# Cokpit_V3-_AutoPilot.net
KiCad netlist of a schematic drawn in EasyEDA
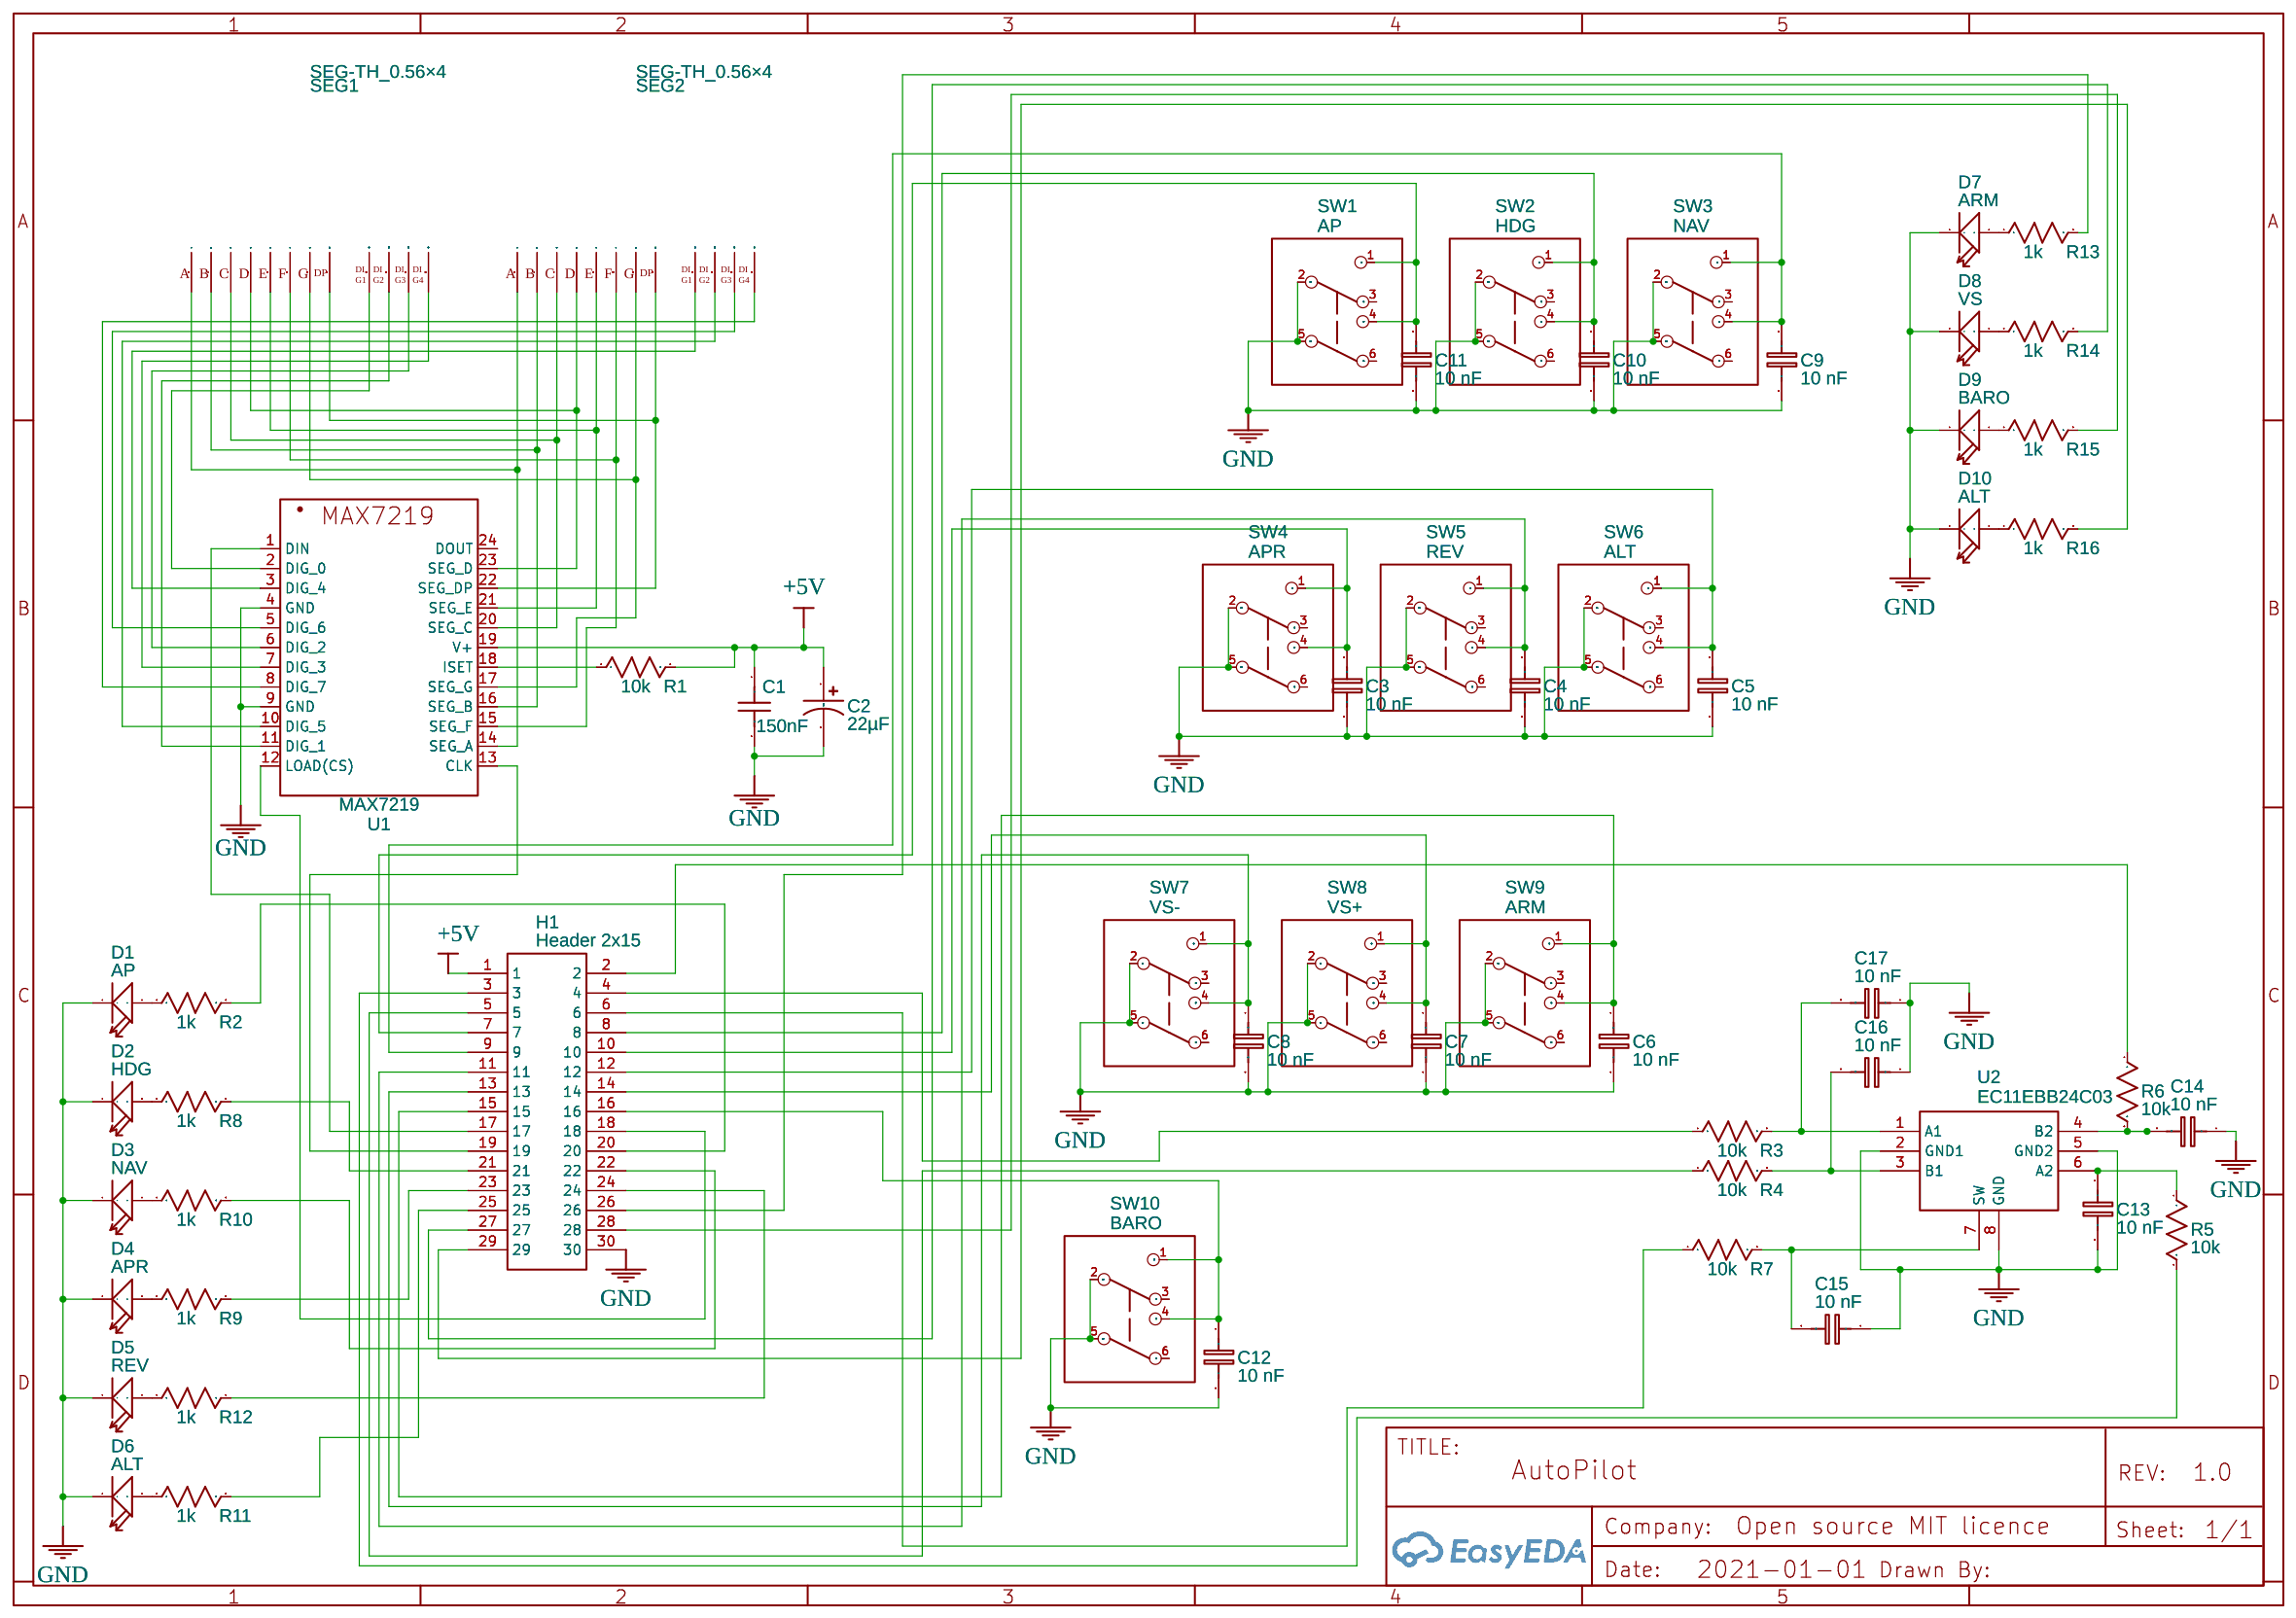
[diagram p0: schematic sheet]

(export (version "E")
  (design (tool "Eeschema 10.0.6"))
  (components
    (comp (ref "C1") (value "150nF") (libsource (lib "") (part "C_0201_US")))
    (comp (ref "C2") (value "22µF") (libsource (lib "") (part "C_Tan_SMD_A_US")))
    (comp (ref "C3") (value "10 nF") (libsource (lib "") (part "Capacitor1_EU_1")))
    (comp (ref "C4") (value "10 nF") (libsource (lib "") (part "Capacitor1_EU_1")))
    (comp (ref "C5") (value "10 nF") (libsource (lib "") (part "Capacitor1_EU_1")))
    (comp (ref "C6") (value "10 nF") (libsource (lib "") (part "Capacitor1_EU_1")))
    (comp (ref "C7") (value "10 nF") (libsource (lib "") (part "Capacitor1_EU_1")))
    (comp (ref "C8") (value "10 nF") (libsource (lib "") (part "Capacitor1_EU_1")))
    (comp (ref "C9") (value "10 nF") (libsource (lib "") (part "Capacitor1_EU")))
    (comp (ref "C10") (value "10 nF") (libsource (lib "") (part "Capacitor1_EU")))
    (comp (ref "C11") (value "10 nF") (libsource (lib "") (part "Capacitor1_EU")))
    (comp (ref "C12") (value "10 nF") (libsource (lib "") (part "Capacitor1_EU")))
    (comp (ref "C13") (value "10 nF") (libsource (lib "") (part "Capacitor1_EU_1")))
    (comp (ref "C14") (value "10 nF") (libsource (lib "") (part "Capacitor1_EU_2")))
    (comp (ref "C15") (value "10 nF") (libsource (lib "") (part "Capacitor1_EU_2")))
    (comp (ref "C16") (value "10 nF") (libsource (lib "") (part "Capacitor1_EU_2")))
    (comp (ref "C17") (value "10 nF") (libsource (lib "") (part "Capacitor1_EU_2")))
    (comp (ref "D1")
      (value "AP")
      (fields (field (name "BOM_Manufacturer Part") "?"))
      (libsource (lib "") (part "DIP LED Red-Red;"))
    )
    (comp (ref "D2")
      (value "HDG")
      (fields (field (name "BOM_Manufacturer Part") "?"))
      (libsource (lib "") (part "DIP LED Red-Red;"))
    )
    (comp (ref "D3")
      (value "NAV")
      (fields (field (name "BOM_Manufacturer Part") "?"))
      (libsource (lib "") (part "DIP LED Red-Red;"))
    )
    (comp (ref "D4")
      (value "APR")
      (fields (field (name "BOM_Manufacturer Part") "?"))
      (libsource (lib "") (part "DIP LED Red-Red;"))
    )
    (comp (ref "D5")
      (value "REV")
      (fields (field (name "BOM_Manufacturer Part") "?"))
      (libsource (lib "") (part "DIP LED Red-Red;"))
    )
    (comp (ref "D6")
      (value "ALT")
      (fields (field (name "BOM_Manufacturer Part") "?"))
      (libsource (lib "") (part "DIP LED Red-Red;"))
    )
    (comp (ref "D7")
      (value "ARM")
      (fields (field (name "BOM_Manufacturer Part") "?"))
      (libsource (lib "") (part "DIP LED Red-Red;"))
    )
    (comp (ref "D8")
      (value "VS")
      (fields (field (name "BOM_Manufacturer Part") "?"))
      (libsource (lib "") (part "DIP LED Red-Red;"))
    )
    (comp (ref "D9")
      (value "BARO")
      (fields (field (name "BOM_Manufacturer Part") "?"))
      (libsource (lib "") (part "DIP LED Red-Red;"))
    )
    (comp (ref "D10")
      (value "ALT")
      (fields (field (name "BOM_Manufacturer Part") "?"))
      (libsource (lib "") (part "DIP LED Red-Red;"))
    )
    (comp (ref "H1") (value "Header 2x15") (libsource (lib "") (part "Header 2x15")))
    (comp (ref "R1") (value "10k") (libsource (lib "") (part "R_0201_US")))
    (comp (ref "R2") (value "1k") (libsource (lib "") (part "R_0201_US")))
    (comp (ref "R3") (value "10k") (libsource (lib "") (part "R_0201_US")))
    (comp (ref "R4") (value "10k") (libsource (lib "") (part "R_0201_US")))
    (comp (ref "R5") (value "10k") (libsource (lib "") (part "R_0201_US_1")))
    (comp (ref "R6") (value "10k") (libsource (lib "") (part "R_0201_US_1")))
    (comp (ref "R7") (value "10k") (libsource (lib "") (part "R_0201_US")))
    (comp (ref "R8") (value "1k") (libsource (lib "") (part "R_0201_US")))
    (comp (ref "R9") (value "1k") (libsource (lib "") (part "R_0201_US")))
    (comp (ref "R10") (value "1k") (libsource (lib "") (part "R_0201_US")))
    (comp (ref "R11") (value "1k") (libsource (lib "") (part "R_0201_US")))
    (comp (ref "R12") (value "1k") (libsource (lib "") (part "R_0201_US")))
    (comp (ref "R13") (value "1k") (libsource (lib "") (part "R_0201_US")))
    (comp (ref "R14") (value "1k") (libsource (lib "") (part "R_0201_US")))
    (comp (ref "R15") (value "1k") (libsource (lib "") (part "R_0201_US")))
    (comp (ref "R16") (value "1k") (libsource (lib "") (part "R_0201_US")))
    (comp (ref "SEG1")
      (value "SEG-TH_0.56×4")
      (fields (field (name "BOM_Supplier Part") "C109200"))
      (libsource (lib "") (part "SEG-TH_0.56×4"))
    )
    (comp (ref "SEG2")
      (value "SEG-TH_0.56×4")
      (fields (field (name "BOM_Supplier Part") "C109200"))
      (libsource (lib "") (part "SEG-TH_0.56×4"))
    )
    (comp (ref "SW1") (value "AP") (libsource (lib "") (part "SW_PUSH_DPDT_MINI_7x7")))
    (comp (ref "SW2") (value "HDG") (libsource (lib "") (part "SW_PUSH_DPDT_MINI_7x7")))
    (comp (ref "SW3") (value "NAV") (libsource (lib "") (part "SW_PUSH_DPDT_MINI_7x7")))
    (comp (ref "SW4") (value "APR") (libsource (lib "") (part "SW_PUSH_DPDT_MINI_7x7")))
    (comp (ref "SW5") (value "REV") (libsource (lib "") (part "SW_PUSH_DPDT_MINI_7x7")))
    (comp (ref "SW6") (value "ALT") (libsource (lib "") (part "SW_PUSH_DPDT_MINI_7x7")))
    (comp (ref "SW7") (value "VS-") (libsource (lib "") (part "SW_PUSH_DPDT_MINI_7x7")))
    (comp (ref "SW8") (value "VS+") (libsource (lib "") (part "SW_PUSH_DPDT_MINI_7x7")))
    (comp (ref "SW9") (value "ARM") (libsource (lib "") (part "SW_PUSH_DPDT_MINI_7x7")))
    (comp (ref "SW10") (value "BARO") (libsource (lib "") (part "SW_PUSH_DPDT_MINI_7x7")))
    (comp (ref "U1")
      (value "MAX7219")
      (fields (field (name "BOM_Manufacturer Part") "MAXIM") (field (name "BOM_Supplier Part") "C129565"))
      (libsource (lib "") (part "MAX7219"))
    )
    (comp (ref "U2") (value "EC11EBB24C03") (libsource (lib "") (part "EC11EBB24C03")))
  )
  (nets
    (net (code "1") (name "+5V") (class "Default")
      (node (ref "C1") (pin "1") (pinfunction "1_1") (pintype "unspecified"))
      (node (ref "C2") (pin "1") (pinfunction "1_1") (pintype "unspecified"))
      (node (ref "H1") (pin "1") (pinfunction "1_1") (pintype "unspecified"))
      (node (ref "R1") (pin "2") (pinfunction "2_2") (pintype "unspecified"))
      (node (ref "U1") (pin "19") (pinfunction "V+_19") (pintype "unspecified"))
    )
    (net (code "2") (name "GND") (class "Default")
      (node (ref "C1") (pin "2") (pinfunction "2_2") (pintype "unspecified"))
      (node (ref "C10") (pin "2") (pinfunction "2_2") (pintype "unspecified"))
      (node (ref "C11") (pin "2") (pinfunction "2_2") (pintype "unspecified"))
      (node (ref "C12") (pin "2") (pinfunction "2_2") (pintype "unspecified"))
      (node (ref "C13") (pin "2") (pinfunction "2_2") (pintype "unspecified"))
      (node (ref "C14") (pin "1") (pinfunction "1_1") (pintype "unspecified"))
      (node (ref "C15") (pin "1") (pinfunction "1_1") (pintype "unspecified"))
      (node (ref "C16") (pin "1") (pinfunction "1_1") (pintype "unspecified"))
      (node (ref "C17") (pin "1") (pinfunction "1_1") (pintype "unspecified"))
      (node (ref "C2") (pin "2") (pinfunction "2_2") (pintype "unspecified"))
      (node (ref "C3") (pin "2") (pinfunction "2_2") (pintype "unspecified"))
      (node (ref "C4") (pin "2") (pinfunction "2_2") (pintype "unspecified"))
      (node (ref "C5") (pin "2") (pinfunction "2_2") (pintype "unspecified"))
      (node (ref "C6") (pin "2") (pinfunction "2_2") (pintype "unspecified"))
      (node (ref "C7") (pin "2") (pinfunction "2_2") (pintype "unspecified"))
      (node (ref "C8") (pin "2") (pinfunction "2_2") (pintype "unspecified"))
      (node (ref "C9") (pin "2") (pinfunction "2_2") (pintype "unspecified"))
      (node (ref "D1") (pin "K") (pinfunction "-_K") (pintype "unspecified"))
      (node (ref "D10") (pin "K") (pinfunction "-_K") (pintype "unspecified"))
      (node (ref "D2") (pin "K") (pinfunction "-_K") (pintype "unspecified"))
      (node (ref "D3") (pin "K") (pinfunction "-_K") (pintype "unspecified"))
      (node (ref "D4") (pin "K") (pinfunction "-_K") (pintype "unspecified"))
      (node (ref "D5") (pin "K") (pinfunction "-_K") (pintype "unspecified"))
      (node (ref "D6") (pin "K") (pinfunction "-_K") (pintype "unspecified"))
      (node (ref "D7") (pin "K") (pinfunction "-_K") (pintype "unspecified"))
      (node (ref "D8") (pin "K") (pinfunction "-_K") (pintype "unspecified"))
      (node (ref "D9") (pin "K") (pinfunction "-_K") (pintype "unspecified"))
      (node (ref "H1") (pin "30") (pinfunction "30_30") (pintype "unspecified"))
      (node (ref "SW1") (pin "2") (pinfunction "COM1_2") (pintype "unspecified"))
      (node (ref "SW1") (pin "5") (pinfunction "COM2_5") (pintype "unspecified"))
      (node (ref "SW10") (pin "2") (pinfunction "COM1_2") (pintype "unspecified"))
      (node (ref "SW10") (pin "5") (pinfunction "COM2_5") (pintype "unspecified"))
      (node (ref "SW2") (pin "2") (pinfunction "COM1_2") (pintype "unspecified"))
      (node (ref "SW2") (pin "5") (pinfunction "COM2_5") (pintype "unspecified"))
      (node (ref "SW3") (pin "2") (pinfunction "COM1_2") (pintype "unspecified"))
      (node (ref "SW3") (pin "5") (pinfunction "COM2_5") (pintype "unspecified"))
      (node (ref "SW4") (pin "2") (pinfunction "COM1_2") (pintype "unspecified"))
      (node (ref "SW4") (pin "5") (pinfunction "COM2_5") (pintype "unspecified"))
      (node (ref "SW5") (pin "2") (pinfunction "COM1_2") (pintype "unspecified"))
      (node (ref "SW5") (pin "5") (pinfunction "COM2_5") (pintype "unspecified"))
      (node (ref "SW6") (pin "2") (pinfunction "COM1_2") (pintype "unspecified"))
      (node (ref "SW6") (pin "5") (pinfunction "COM2_5") (pintype "unspecified"))
      (node (ref "SW7") (pin "2") (pinfunction "COM1_2") (pintype "unspecified"))
      (node (ref "SW7") (pin "5") (pinfunction "COM2_5") (pintype "unspecified"))
      (node (ref "SW8") (pin "2") (pinfunction "COM1_2") (pintype "unspecified"))
      (node (ref "SW8") (pin "5") (pinfunction "COM2_5") (pintype "unspecified"))
      (node (ref "SW9") (pin "2") (pinfunction "COM1_2") (pintype "unspecified"))
      (node (ref "SW9") (pin "5") (pinfunction "COM2_5") (pintype "unspecified"))
      (node (ref "U1") (pin "4") (pinfunction "GND_4") (pintype "unspecified"))
      (node (ref "U1") (pin "9") (pinfunction "GND_9") (pintype "unspecified"))
      (node (ref "U2") (pin "2") (pinfunction "GND1_2") (pintype "unspecified"))
      (node (ref "U2") (pin "5") (pinfunction "GND2_5") (pintype "unspecified"))
      (node (ref "U2") (pin "8") (pinfunction "GND_8") (pintype "unspecified"))
    )
    (net (code "3") (name "Net-(D1-+)") (class "Default")
      (node (ref "D1") (pin "A") (pinfunction "+_A") (pintype "unspecified"))
      (node (ref "R2") (pin "1") (pinfunction "1_1") (pintype "unspecified"))
    )
    (net (code "4") (name "Net-(D2-+)") (class "Default")
      (node (ref "D2") (pin "A") (pinfunction "+_A") (pintype "unspecified"))
      (node (ref "R8") (pin "1") (pinfunction "1_1") (pintype "unspecified"))
    )
    (net (code "5") (name "Net-(D3-+)") (class "Default")
      (node (ref "D3") (pin "A") (pinfunction "+_A") (pintype "unspecified"))
      (node (ref "R10") (pin "1") (pinfunction "1_1") (pintype "unspecified"))
    )
    (net (code "6") (name "Net-(D4-+)") (class "Default")
      (node (ref "D4") (pin "A") (pinfunction "+_A") (pintype "unspecified"))
      (node (ref "R9") (pin "1") (pinfunction "1_1") (pintype "unspecified"))
    )
    (net (code "7") (name "Net-(D5-+)") (class "Default")
      (node (ref "D5") (pin "A") (pinfunction "+_A") (pintype "unspecified"))
      (node (ref "R12") (pin "1") (pinfunction "1_1") (pintype "unspecified"))
    )
    (net (code "8") (name "Net-(D6-+)") (class "Default")
      (node (ref "D6") (pin "A") (pinfunction "+_A") (pintype "unspecified"))
      (node (ref "R11") (pin "1") (pinfunction "1_1") (pintype "unspecified"))
    )
    (net (code "9") (name "Net-(D7-+)") (class "Default")
      (node (ref "D7") (pin "A") (pinfunction "+_A") (pintype "unspecified"))
      (node (ref "R13") (pin "1") (pinfunction "1_1") (pintype "unspecified"))
    )
    (net (code "10") (name "Net-(D8-+)") (class "Default")
      (node (ref "D8") (pin "A") (pinfunction "+_A") (pintype "unspecified"))
      (node (ref "R14") (pin "1") (pinfunction "1_1") (pintype "unspecified"))
    )
    (net (code "11") (name "Net-(D9-+)") (class "Default")
      (node (ref "D9") (pin "A") (pinfunction "+_A") (pintype "unspecified"))
      (node (ref "R15") (pin "1") (pinfunction "1_1") (pintype "unspecified"))
    )
    (net (code "12") (name "Net-(D10-+)") (class "Default")
      (node (ref "D10") (pin "A") (pinfunction "+_A") (pintype "unspecified"))
      (node (ref "R16") (pin "1") (pinfunction "1_1") (pintype "unspecified"))
    )
    (net (code "13") (name "Net-(H1-Pad2)") (class "Default")
      (node (ref "H1") (pin "2") (pinfunction "2_2") (pintype "unspecified"))
      (node (ref "R6") (pin "1") (pinfunction "1_1") (pintype "unspecified"))
    )
    (net (code "14") (name "Net-(H1-Pad3)") (class "Default")
      (node (ref "H1") (pin "3") (pinfunction "3_3") (pintype "unspecified"))
      (node (ref "R5") (pin "2") (pinfunction "2_2") (pintype "unspecified"))
    )
    (net (code "15") (name "Net-(H1-Pad4)") (class "Default")
      (node (ref "H1") (pin "4") (pinfunction "4_4") (pintype "unspecified"))
      (node (ref "R3") (pin "1") (pinfunction "1_1") (pintype "unspecified"))
    )
    (net (code "16") (name "Net-(H1-Pad5)") (class "Default")
      (node (ref "H1") (pin "5") (pinfunction "5_5") (pintype "unspecified"))
      (node (ref "R4") (pin "1") (pinfunction "1_1") (pintype "unspecified"))
    )
    (net (code "17") (name "Net-(H1-Pad6)") (class "Default")
      (node (ref "H1") (pin "6") (pinfunction "6_6") (pintype "unspecified"))
      (node (ref "R7") (pin "1") (pinfunction "1_1") (pintype "unspecified"))
    )
    (net (code "18") (name "Net-(H1-Pad20)") (class "Default")
      (node (ref "H1") (pin "20") (pinfunction "20_20") (pintype "unspecified"))
      (node (ref "R2") (pin "2") (pinfunction "2_2") (pintype "unspecified"))
    )
    (net (code "19") (name "Net-(H1-Pad21)") (class "Default")
      (node (ref "H1") (pin "21") (pinfunction "21_21") (pintype "unspecified"))
      (node (ref "R8") (pin "2") (pinfunction "2_2") (pintype "unspecified"))
    )
    (net (code "20") (name "Net-(H1-Pad22)") (class "Default")
      (node (ref "H1") (pin "22") (pinfunction "22_22") (pintype "unspecified"))
      (node (ref "R10") (pin "2") (pinfunction "2_2") (pintype "unspecified"))
    )
    (net (code "21") (name "Net-(H1-Pad23)") (class "Default")
      (node (ref "H1") (pin "23") (pinfunction "23_23") (pintype "unspecified"))
      (node (ref "R9") (pin "2") (pinfunction "2_2") (pintype "unspecified"))
    )
    (net (code "22") (name "Net-(H1-Pad24)") (class "Default")
      (node (ref "H1") (pin "24") (pinfunction "24_24") (pintype "unspecified"))
      (node (ref "R12") (pin "2") (pinfunction "2_2") (pintype "unspecified"))
    )
    (net (code "23") (name "Net-(H1-Pad25)") (class "Default")
      (node (ref "H1") (pin "25") (pinfunction "25_25") (pintype "unspecified"))
      (node (ref "R11") (pin "2") (pinfunction "2_2") (pintype "unspecified"))
    )
    (net (code "24") (name "Net-(H1-Pad26)") (class "Default")
      (node (ref "H1") (pin "26") (pinfunction "26_26") (pintype "unspecified"))
      (node (ref "R13") (pin "2") (pinfunction "2_2") (pintype "unspecified"))
    )
    (net (code "25") (name "Net-(H1-Pad27)") (class "Default")
      (node (ref "H1") (pin "27") (pinfunction "27_27") (pintype "unspecified"))
      (node (ref "R14") (pin "2") (pinfunction "2_2") (pintype "unspecified"))
    )
    (net (code "26") (name "Net-(H1-Pad28)") (class "Default")
      (node (ref "H1") (pin "28") (pinfunction "28_28") (pintype "unspecified"))
      (node (ref "R15") (pin "2") (pinfunction "2_2") (pintype "unspecified"))
    )
    (net (code "27") (name "Net-(H1-Pad29)") (class "Default")
      (node (ref "H1") (pin "29") (pinfunction "29_29") (pintype "unspecified"))
      (node (ref "R16") (pin "2") (pinfunction "2_2") (pintype "unspecified"))
    )
    (net (code "28") (name "Net-(SEG1-A)") (class "Default")
      (node (ref "SEG1") (pin "11") (pinfunction "A_11") (pintype "input"))
      (node (ref "SEG2") (pin "11") (pinfunction "A_11") (pintype "input"))
      (node (ref "U1") (pin "14") (pinfunction "SEG_A_14") (pintype "unspecified"))
    )
    (net (code "29") (name "Net-(SEG1-B)") (class "Default")
      (node (ref "SEG1") (pin "7") (pinfunction "B_7") (pintype "input"))
      (node (ref "SEG2") (pin "7") (pinfunction "B_7") (pintype "input"))
      (node (ref "U1") (pin "16") (pinfunction "SEG_B_16") (pintype "unspecified"))
    )
    (net (code "30") (name "Net-(SEG1-C)") (class "Default")
      (node (ref "SEG1") (pin "4") (pinfunction "C_4") (pintype "input"))
      (node (ref "SEG2") (pin "4") (pinfunction "C_4") (pintype "input"))
      (node (ref "U1") (pin "20") (pinfunction "SEG_C_20") (pintype "unspecified"))
    )
    (net (code "31") (name "Net-(SEG1-D)") (class "Default")
      (node (ref "SEG1") (pin "2") (pinfunction "D_2") (pintype "input"))
      (node (ref "SEG2") (pin "2") (pinfunction "D_2") (pintype "input"))
      (node (ref "U1") (pin "23") (pinfunction "SEG_D_23") (pintype "unspecified"))
    )
    (net (code "32") (name "Net-(SEG1-DIG1)") (class "Default")
      (node (ref "SEG1") (pin "12") (pinfunction "DIG1_12") (pintype "input"))
      (node (ref "U1") (pin "2") (pinfunction "DIG_0_2") (pintype "unspecified"))
    )
    (net (code "33") (name "Net-(SEG1-DIG2)") (class "Default")
      (node (ref "SEG1") (pin "9") (pinfunction "DIG2_9") (pintype "input"))
      (node (ref "U1") (pin "11") (pinfunction "DIG_1_11") (pintype "unspecified"))
    )
    (net (code "34") (name "Net-(SEG1-DIG3)") (class "Default")
      (node (ref "SEG1") (pin "8") (pinfunction "DIG3_8") (pintype "input"))
      (node (ref "U1") (pin "6") (pinfunction "DIG_2_6") (pintype "unspecified"))
    )
    (net (code "35") (name "Net-(SEG1-DIG4)") (class "Default")
      (node (ref "SEG1") (pin "6") (pinfunction "DIG4_6") (pintype "input"))
      (node (ref "U1") (pin "7") (pinfunction "DIG_3_7") (pintype "unspecified"))
    )
    (net (code "36") (name "Net-(SEG1-DP)") (class "Default")
      (node (ref "SEG1") (pin "3") (pinfunction "DP_3") (pintype "input"))
      (node (ref "SEG2") (pin "3") (pinfunction "DP_3") (pintype "input"))
      (node (ref "U1") (pin "22") (pinfunction "SEG_DP_22") (pintype "unspecified"))
    )
    (net (code "37") (name "Net-(SEG1-E)") (class "Default")
      (node (ref "SEG1") (pin "1") (pinfunction "E_1") (pintype "input"))
      (node (ref "SEG2") (pin "1") (pinfunction "E_1") (pintype "input"))
      (node (ref "U1") (pin "21") (pinfunction "SEG_E_21") (pintype "unspecified"))
    )
    (net (code "38") (name "Net-(SEG1-F)") (class "Default")
      (node (ref "SEG1") (pin "10") (pinfunction "F_10") (pintype "input"))
      (node (ref "SEG2") (pin "10") (pinfunction "F_10") (pintype "input"))
      (node (ref "U1") (pin "15") (pinfunction "SEG_F_15") (pintype "unspecified"))
    )
    (net (code "39") (name "Net-(SEG1-G)") (class "Default")
      (node (ref "SEG1") (pin "5") (pinfunction "G_5") (pintype "input"))
      (node (ref "SEG2") (pin "5") (pinfunction "G_5") (pintype "input"))
      (node (ref "U1") (pin "17") (pinfunction "SEG_G_17") (pintype "unspecified"))
    )
    (net (code "40") (name "Net-(SEG2-DIG1)") (class "Default")
      (node (ref "SEG2") (pin "12") (pinfunction "DIG1_12") (pintype "input"))
      (node (ref "U1") (pin "3") (pinfunction "DIG_4_3") (pintype "unspecified"))
    )
    (net (code "41") (name "Net-(SEG2-DIG2)") (class "Default")
      (node (ref "SEG2") (pin "9") (pinfunction "DIG2_9") (pintype "input"))
      (node (ref "U1") (pin "10") (pinfunction "DIG_5_10") (pintype "unspecified"))
    )
    (net (code "42") (name "Net-(SEG2-DIG3)") (class "Default")
      (node (ref "SEG2") (pin "8") (pinfunction "DIG3_8") (pintype "input"))
      (node (ref "U1") (pin "5") (pinfunction "DIG_6_5") (pintype "unspecified"))
    )
    (net (code "43") (name "Net-(SEG2-DIG4)") (class "Default")
      (node (ref "SEG2") (pin "6") (pinfunction "DIG4_6") (pintype "input"))
      (node (ref "U1") (pin "8") (pinfunction "DIG_7_8") (pintype "unspecified"))
    )
    (net (code "44") (name "Net-(SW1-NO1)") (class "Default")
      (node (ref "C11") (pin "1") (pinfunction "1_1") (pintype "unspecified"))
      (node (ref "H1") (pin "7") (pinfunction "7_7") (pintype "unspecified"))
      (node (ref "SW1") (pin "1") (pinfunction "NO1_1") (pintype "unspecified"))
      (node (ref "SW1") (pin "4") (pinfunction "NO2_4") (pintype "unspecified"))
    )
    (net (code "45") (name "Net-(SW2-NO1)") (class "Default")
      (node (ref "C10") (pin "1") (pinfunction "1_1") (pintype "unspecified"))
      (node (ref "H1") (pin "8") (pinfunction "8_8") (pintype "unspecified"))
      (node (ref "SW2") (pin "1") (pinfunction "NO1_1") (pintype "unspecified"))
      (node (ref "SW2") (pin "4") (pinfunction "NO2_4") (pintype "unspecified"))
    )
    (net (code "46") (name "Net-(SW3-NO1)") (class "Default")
      (node (ref "C9") (pin "1") (pinfunction "1_1") (pintype "unspecified"))
      (node (ref "H1") (pin "9") (pinfunction "9_9") (pintype "unspecified"))
      (node (ref "SW3") (pin "1") (pinfunction "NO1_1") (pintype "unspecified"))
      (node (ref "SW3") (pin "4") (pinfunction "NO2_4") (pintype "unspecified"))
    )
    (net (code "47") (name "Net-(SW4-NO1)") (class "Default")
      (node (ref "C3") (pin "1") (pinfunction "1_1") (pintype "unspecified"))
      (node (ref "H1") (pin "10") (pinfunction "10_10") (pintype "unspecified"))
      (node (ref "SW4") (pin "1") (pinfunction "NO1_1") (pintype "unspecified"))
      (node (ref "SW4") (pin "4") (pinfunction "NO2_4") (pintype "unspecified"))
    )
    (net (code "48") (name "Net-(SW5-NO1)") (class "Default")
      (node (ref "C4") (pin "1") (pinfunction "1_1") (pintype "unspecified"))
      (node (ref "H1") (pin "11") (pinfunction "11_11") (pintype "unspecified"))
      (node (ref "SW5") (pin "1") (pinfunction "NO1_1") (pintype "unspecified"))
      (node (ref "SW5") (pin "4") (pinfunction "NO2_4") (pintype "unspecified"))
    )
    (net (code "49") (name "Net-(SW6-NO1)") (class "Default")
      (node (ref "C5") (pin "1") (pinfunction "1_1") (pintype "unspecified"))
      (node (ref "H1") (pin "12") (pinfunction "12_12") (pintype "unspecified"))
      (node (ref "SW6") (pin "1") (pinfunction "NO1_1") (pintype "unspecified"))
      (node (ref "SW6") (pin "4") (pinfunction "NO2_4") (pintype "unspecified"))
    )
    (net (code "50") (name "Net-(SW7-NO1)") (class "Default")
      (node (ref "C8") (pin "1") (pinfunction "1_1") (pintype "unspecified"))
      (node (ref "H1") (pin "13") (pinfunction "13_13") (pintype "unspecified"))
      (node (ref "SW7") (pin "1") (pinfunction "NO1_1") (pintype "unspecified"))
      (node (ref "SW7") (pin "4") (pinfunction "NO2_4") (pintype "unspecified"))
    )
    (net (code "51") (name "Net-(SW8-NO1)") (class "Default")
      (node (ref "C7") (pin "1") (pinfunction "1_1") (pintype "unspecified"))
      (node (ref "H1") (pin "14") (pinfunction "14_14") (pintype "unspecified"))
      (node (ref "SW8") (pin "1") (pinfunction "NO1_1") (pintype "unspecified"))
      (node (ref "SW8") (pin "4") (pinfunction "NO2_4") (pintype "unspecified"))
    )
    (net (code "52") (name "Net-(SW9-NO1)") (class "Default")
      (node (ref "C6") (pin "1") (pinfunction "1_1") (pintype "unspecified"))
      (node (ref "H1") (pin "15") (pinfunction "15_15") (pintype "unspecified"))
      (node (ref "SW9") (pin "1") (pinfunction "NO1_1") (pintype "unspecified"))
      (node (ref "SW9") (pin "4") (pinfunction "NO2_4") (pintype "unspecified"))
    )
    (net (code "53") (name "Net-(SW10-NO1)") (class "Default")
      (node (ref "C12") (pin "1") (pinfunction "1_1") (pintype "unspecified"))
      (node (ref "H1") (pin "16") (pinfunction "16_16") (pintype "unspecified"))
      (node (ref "SW10") (pin "1") (pinfunction "NO1_1") (pintype "unspecified"))
      (node (ref "SW10") (pin "4") (pinfunction "NO2_4") (pintype "unspecified"))
    )
    (net (code "54") (name "Net-(U1-CLK)") (class "Default")
      (node (ref "H1") (pin "19") (pinfunction "19_19") (pintype "unspecified"))
      (node (ref "U1") (pin "13") (pinfunction "CLK_13") (pintype "unspecified"))
    )
    (net (code "55") (name "Net-(U1-DIN)") (class "Default")
      (node (ref "H1") (pin "17") (pinfunction "17_17") (pintype "unspecified"))
      (node (ref "U1") (pin "1") (pinfunction "DIN_1") (pintype "unspecified"))
    )
    (net (code "56") (name "Net-(U1-ISET)") (class "Default")
      (node (ref "R1") (pin "1") (pinfunction "1_1") (pintype "unspecified"))
      (node (ref "U1") (pin "18") (pinfunction "ISET_18") (pintype "unspecified"))
    )
    (net (code "57") (name "Net-(U1-LOAD(CS))") (class "Default")
      (node (ref "H1") (pin "18") (pinfunction "18_18") (pintype "unspecified"))
      (node (ref "U1") (pin "12") (pinfunction "LOAD(CS)_12") (pintype "unspecified"))
    )
    (net (code "58") (name "Net-(U2-A1)") (class "Default")
      (node (ref "C17") (pin "2") (pinfunction "2_2") (pintype "unspecified"))
      (node (ref "R3") (pin "2") (pinfunction "2_2") (pintype "unspecified"))
      (node (ref "U2") (pin "1") (pinfunction "A1_1") (pintype "unspecified"))
    )
    (net (code "59") (name "Net-(U2-A2)") (class "Default")
      (node (ref "C13") (pin "1") (pinfunction "1_1") (pintype "unspecified"))
      (node (ref "R5") (pin "1") (pinfunction "1_1") (pintype "unspecified"))
      (node (ref "U2") (pin "6") (pinfunction "A2_6") (pintype "unspecified"))
    )
    (net (code "60") (name "Net-(U2-B1)") (class "Default")
      (node (ref "C16") (pin "2") (pinfunction "2_2") (pintype "unspecified"))
      (node (ref "R4") (pin "2") (pinfunction "2_2") (pintype "unspecified"))
      (node (ref "U2") (pin "3") (pinfunction "B1_3") (pintype "unspecified"))
    )
    (net (code "61") (name "Net-(U2-B2)") (class "Default")
      (node (ref "C14") (pin "2") (pinfunction "2_2") (pintype "unspecified"))
      (node (ref "R6") (pin "2") (pinfunction "2_2") (pintype "unspecified"))
      (node (ref "U2") (pin "4") (pinfunction "B2_4") (pintype "unspecified"))
    )
    (net (code "62") (name "Net-(U2-SW)") (class "Default")
      (node (ref "C15") (pin "2") (pinfunction "2_2") (pintype "unspecified"))
      (node (ref "R7") (pin "2") (pinfunction "2_2") (pintype "unspecified"))
      (node (ref "U2") (pin "7") (pinfunction "SW_7") (pintype "unspecified"))
    )
    (net (code "63") (name "unconnected-(SW1-NC1-Pad3)") (class "Default")
      (node (ref "SW1") (pin "3") (pinfunction "NC1_3") (pintype "unspecified"))
    )
    (net (code "64") (name "unconnected-(SW1-NC2-Pad6)") (class "Default")
      (node (ref "SW1") (pin "6") (pinfunction "NC2_6") (pintype "unspecified"))
    )
    (net (code "65") (name "unconnected-(SW2-NC1-Pad3)") (class "Default")
      (node (ref "SW2") (pin "3") (pinfunction "NC1_3") (pintype "unspecified"))
    )
    (net (code "66") (name "unconnected-(SW2-NC2-Pad6)") (class "Default")
      (node (ref "SW2") (pin "6") (pinfunction "NC2_6") (pintype "unspecified"))
    )
    (net (code "67") (name "unconnected-(SW3-NC1-Pad3)") (class "Default")
      (node (ref "SW3") (pin "3") (pinfunction "NC1_3") (pintype "unspecified"))
    )
    (net (code "68") (name "unconnected-(SW3-NC2-Pad6)") (class "Default")
      (node (ref "SW3") (pin "6") (pinfunction "NC2_6") (pintype "unspecified"))
    )
    (net (code "69") (name "unconnected-(SW4-NC1-Pad3)") (class "Default")
      (node (ref "SW4") (pin "3") (pinfunction "NC1_3") (pintype "unspecified"))
    )
    (net (code "70") (name "unconnected-(SW4-NC2-Pad6)") (class "Default")
      (node (ref "SW4") (pin "6") (pinfunction "NC2_6") (pintype "unspecified"))
    )
    (net (code "71") (name "unconnected-(SW5-NC1-Pad3)") (class "Default")
      (node (ref "SW5") (pin "3") (pinfunction "NC1_3") (pintype "unspecified"))
    )
    (net (code "72") (name "unconnected-(SW5-NC2-Pad6)") (class "Default")
      (node (ref "SW5") (pin "6") (pinfunction "NC2_6") (pintype "unspecified"))
    )
    (net (code "73") (name "unconnected-(SW6-NC1-Pad3)") (class "Default")
      (node (ref "SW6") (pin "3") (pinfunction "NC1_3") (pintype "unspecified"))
    )
    (net (code "74") (name "unconnected-(SW6-NC2-Pad6)") (class "Default")
      (node (ref "SW6") (pin "6") (pinfunction "NC2_6") (pintype "unspecified"))
    )
    (net (code "75") (name "unconnected-(SW7-NC1-Pad3)") (class "Default")
      (node (ref "SW7") (pin "3") (pinfunction "NC1_3") (pintype "unspecified"))
    )
    (net (code "76") (name "unconnected-(SW7-NC2-Pad6)") (class "Default")
      (node (ref "SW7") (pin "6") (pinfunction "NC2_6") (pintype "unspecified"))
    )
    (net (code "77") (name "unconnected-(SW8-NC1-Pad3)") (class "Default")
      (node (ref "SW8") (pin "3") (pinfunction "NC1_3") (pintype "unspecified"))
    )
    (net (code "78") (name "unconnected-(SW8-NC2-Pad6)") (class "Default")
      (node (ref "SW8") (pin "6") (pinfunction "NC2_6") (pintype "unspecified"))
    )
    (net (code "79") (name "unconnected-(SW9-NC1-Pad3)") (class "Default")
      (node (ref "SW9") (pin "3") (pinfunction "NC1_3") (pintype "unspecified"))
    )
    (net (code "80") (name "unconnected-(SW9-NC2-Pad6)") (class "Default")
      (node (ref "SW9") (pin "6") (pinfunction "NC2_6") (pintype "unspecified"))
    )
    (net (code "81") (name "unconnected-(SW10-NC1-Pad3)") (class "Default")
      (node (ref "SW10") (pin "3") (pinfunction "NC1_3") (pintype "unspecified"))
    )
    (net (code "82") (name "unconnected-(SW10-NC2-Pad6)") (class "Default")
      (node (ref "SW10") (pin "6") (pinfunction "NC2_6") (pintype "unspecified"))
    )
    (net (code "83") (name "unconnected-(U1-DOUT-Pad24)") (class "Default")
      (node (ref "U1") (pin "24") (pinfunction "DOUT_24") (pintype "unspecified"))
    )
  )
)
